# BLOCK2.net
KiCad netlist of a schematic drawn in Altium Designer
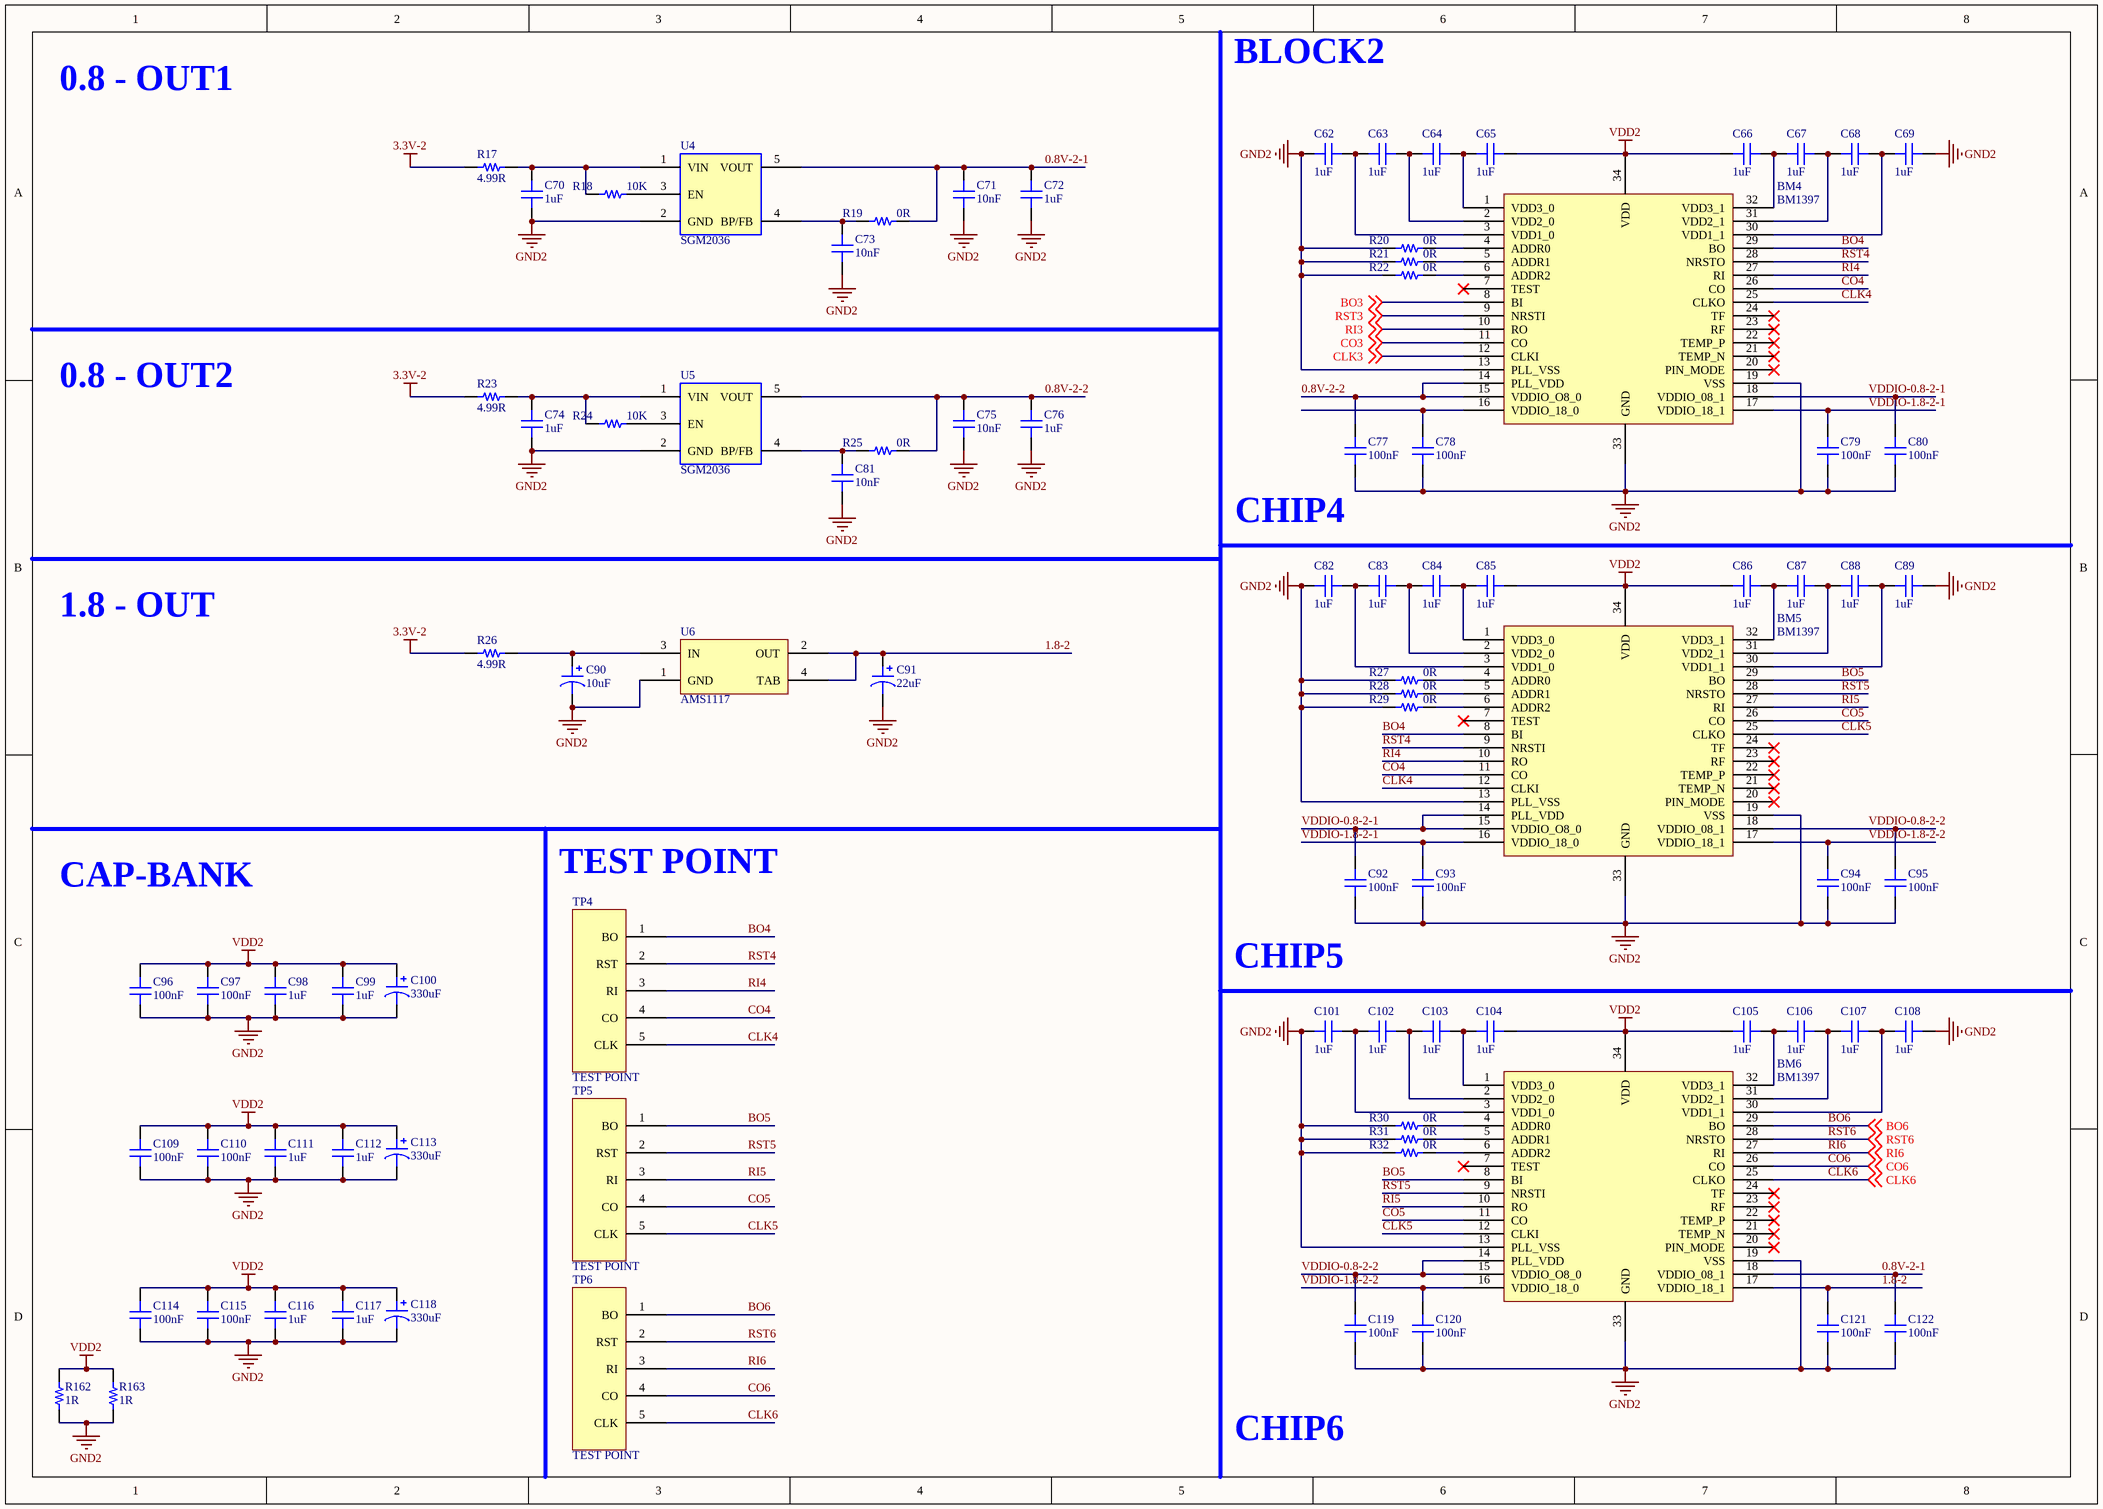
[diagram p0: BLOCK2.SchDoc]

(export (version "E")
  (design (tool "Eeschema 10.0.6"))
  (components
    (comp (ref "BM4") (value "BM1397") (footprint "BM1387") (libsource (lib "Miner_8TH") (part "BM1397_1")))
    (comp (ref "BM5") (value "BM1397") (footprint "BM1387") (libsource (lib "Miner_8TH") (part "BM1397_1")))
    (comp (ref "BM6") (value "BM1397") (footprint "BM1387") (libsource (lib "Miner_8TH") (part "BM1397_1")))
    (comp (ref "C62") (value "1uF") (footprint "CAP-SMD-0603") (libsource (lib "Miner_8TH") (part "CAP")))
    (comp (ref "C63") (value "1uF") (footprint "CAP-SMD-0603") (libsource (lib "Miner_8TH") (part "CAP")))
    (comp (ref "C64") (value "1uF") (footprint "CAP-SMD-0603") (libsource (lib "Miner_8TH") (part "CAP")))
    (comp (ref "C65") (value "1uF") (footprint "CAP-SMD-0603") (libsource (lib "Miner_8TH") (part "CAP")))
    (comp (ref "C66") (value "1uF") (footprint "CAP-SMD-0603") (libsource (lib "Miner_8TH") (part "CAP")))
    (comp (ref "C67") (value "1uF") (footprint "CAP-SMD-0603") (libsource (lib "Miner_8TH") (part "CAP")))
    (comp (ref "C68") (value "1uF") (footprint "CAP-SMD-0603") (libsource (lib "Miner_8TH") (part "CAP")))
    (comp (ref "C69") (value "1uF") (footprint "CAP-SMD-0603") (libsource (lib "Miner_8TH") (part "CAP")))
    (comp (ref "C70") (value "1uF") (footprint "CAP_SMD_0805") (libsource (lib "Miner_8TH") (part "CAP")))
    (comp (ref "C71") (value "10nF") (footprint "CAP_SMD_0805") (libsource (lib "Miner_8TH") (part "CAP")))
    (comp (ref "C72") (value "1uF") (footprint "CAP_SMD_0805") (libsource (lib "Miner_8TH") (part "CAP")))
    (comp (ref "C73") (value "10nF") (footprint "CAP_SMD_0805") (libsource (lib "Miner_8TH") (part "CAP")))
    (comp (ref "C74") (value "1uF") (footprint "CAP_SMD_0805") (libsource (lib "Miner_8TH") (part "CAP")))
    (comp (ref "C75") (value "10nF") (footprint "CAP_SMD_0805") (libsource (lib "Miner_8TH") (part "CAP")))
    (comp (ref "C76") (value "1uF") (footprint "CAP_SMD_0805") (libsource (lib "Miner_8TH") (part "CAP")))
    (comp (ref "C77") (value "100nF") (footprint "CAP_SMD_0805") (libsource (lib "Miner_8TH") (part "CAP")))
    (comp (ref "C78") (value "100nF") (footprint "CAP_SMD_0805") (libsource (lib "Miner_8TH") (part "CAP")))
    (comp (ref "C79") (value "100nF") (footprint "CAP_SMD_0805") (libsource (lib "Miner_8TH") (part "CAP")))
    (comp (ref "C80") (value "100nF") (footprint "CAP_SMD_0805") (libsource (lib "Miner_8TH") (part "CAP")))
    (comp (ref "C81") (value "10nF") (footprint "CAP_SMD_0805") (libsource (lib "Miner_8TH") (part "CAP")))
    (comp (ref "C82") (value "1uF") (footprint "CAP-SMD-0603") (libsource (lib "Miner_8TH") (part "CAP")))
    (comp (ref "C83") (value "1uF") (footprint "CAP-SMD-0603") (libsource (lib "Miner_8TH") (part "CAP")))
    (comp (ref "C84") (value "1uF") (footprint "CAP-SMD-0603") (libsource (lib "Miner_8TH") (part "CAP")))
    (comp (ref "C85") (value "1uF") (footprint "CAP-SMD-0603") (libsource (lib "Miner_8TH") (part "CAP")))
    (comp (ref "C86") (value "1uF") (footprint "CAP-SMD-0603") (libsource (lib "Miner_8TH") (part "CAP")))
    (comp (ref "C87") (value "1uF") (footprint "CAP-SMD-0603") (libsource (lib "Miner_8TH") (part "CAP")))
    (comp (ref "C88") (value "1uF") (footprint "CAP-SMD-0603") (libsource (lib "Miner_8TH") (part "CAP")))
    (comp (ref "C89") (value "1uF") (footprint "CAP-SMD-0603") (libsource (lib "Miner_8TH") (part "CAP")))
    (comp (ref "C90")
      (value "10uF")
      (footprint "CAP-TAN-CASE-A")
      (libsource (lib "Miner_8TH") (part "POLARIZED CAP"))
    )
    (comp (ref "C91")
      (value "22uF")
      (footprint "CAP-TAN-CASE-A")
      (libsource (lib "Miner_8TH") (part "POLARIZED CAP"))
    )
    (comp (ref "C92") (value "100nF") (footprint "CAP_SMD_0805") (libsource (lib "Miner_8TH") (part "CAP")))
    (comp (ref "C93") (value "100nF") (footprint "CAP_SMD_0805") (libsource (lib "Miner_8TH") (part "CAP")))
    (comp (ref "C94") (value "100nF") (footprint "CAP_SMD_0805") (libsource (lib "Miner_8TH") (part "CAP")))
    (comp (ref "C95") (value "100nF") (footprint "CAP_SMD_0805") (libsource (lib "Miner_8TH") (part "CAP")))
    (comp (ref "C96") (value "100nF") (footprint "CAP_SMD_0805") (libsource (lib "Miner_8TH") (part "CAP")))
    (comp (ref "C97") (value "100nF") (footprint "CAP_SMD_0805") (libsource (lib "Miner_8TH") (part "CAP")))
    (comp (ref "C98") (value "1uF") (footprint "CAP_SMD_0805") (libsource (lib "Miner_8TH") (part "CAP")))
    (comp (ref "C99") (value "1uF") (footprint "CAP_SMD_0805") (libsource (lib "Miner_8TH") (part "CAP")))
    (comp (ref "C100")
      (value "330uF")
      (footprint "CAP-TAN-CASE-E")
      (libsource (lib "Miner_8TH") (part "POLARIZED CAP"))
    )
    (comp (ref "C101") (value "1uF") (footprint "CAP-SMD-0603") (libsource (lib "Miner_8TH") (part "CAP")))
    (comp (ref "C102") (value "1uF") (footprint "CAP-SMD-0603") (libsource (lib "Miner_8TH") (part "CAP")))
    (comp (ref "C103") (value "1uF") (footprint "CAP-SMD-0603") (libsource (lib "Miner_8TH") (part "CAP")))
    (comp (ref "C104") (value "1uF") (footprint "CAP-SMD-0603") (libsource (lib "Miner_8TH") (part "CAP")))
    (comp (ref "C105") (value "1uF") (footprint "CAP-SMD-0603") (libsource (lib "Miner_8TH") (part "CAP")))
    (comp (ref "C106") (value "1uF") (footprint "CAP-SMD-0603") (libsource (lib "Miner_8TH") (part "CAP")))
    (comp (ref "C107") (value "1uF") (footprint "CAP-SMD-0603") (libsource (lib "Miner_8TH") (part "CAP")))
    (comp (ref "C108") (value "1uF") (footprint "CAP-SMD-0603") (libsource (lib "Miner_8TH") (part "CAP")))
    (comp (ref "C109") (value "100nF") (footprint "CAP_SMD_0805") (libsource (lib "Miner_8TH") (part "CAP")))
    (comp (ref "C110") (value "100nF") (footprint "CAP_SMD_0805") (libsource (lib "Miner_8TH") (part "CAP")))
    (comp (ref "C111") (value "1uF") (footprint "CAP_SMD_0805") (libsource (lib "Miner_8TH") (part "CAP")))
    (comp (ref "C112") (value "1uF") (footprint "CAP_SMD_0805") (libsource (lib "Miner_8TH") (part "CAP")))
    (comp (ref "C113")
      (value "330uF")
      (footprint "CAP-TAN-CASE-E")
      (libsource (lib "Miner_8TH") (part "POLARIZED CAP"))
    )
    (comp (ref "C114") (value "100nF") (footprint "CAP_SMD_0805") (libsource (lib "Miner_8TH") (part "CAP")))
    (comp (ref "C115") (value "100nF") (footprint "CAP_SMD_0805") (libsource (lib "Miner_8TH") (part "CAP")))
    (comp (ref "C116") (value "1uF") (footprint "CAP_SMD_0805") (libsource (lib "Miner_8TH") (part "CAP")))
    (comp (ref "C117") (value "1uF") (footprint "CAP_SMD_0805") (libsource (lib "Miner_8TH") (part "CAP")))
    (comp (ref "C118")
      (value "330uF")
      (footprint "CAP-TAN-CASE-E")
      (libsource (lib "Miner_8TH") (part "POLARIZED CAP"))
    )
    (comp (ref "C119") (value "100nF") (footprint "CAP_SMD_0805") (libsource (lib "Miner_8TH") (part "CAP")))
    (comp (ref "C120") (value "100nF") (footprint "CAP_SMD_0805") (libsource (lib "Miner_8TH") (part "CAP")))
    (comp (ref "C121") (value "100nF") (footprint "CAP_SMD_0805") (libsource (lib "Miner_8TH") (part "CAP")))
    (comp (ref "C122") (value "100nF") (footprint "CAP_SMD_0805") (libsource (lib "Miner_8TH") (part "CAP")))
    (comp (ref "R17") (value "4.99R") (footprint "RES-SMD-1206") (libsource (lib "Miner_8TH") (part "RES")))
    (comp (ref "R18") (value "10K") (footprint "RES-SMD-0402") (libsource (lib "Miner_8TH") (part "RES")))
    (comp (ref "R19") (value "0R") (footprint "RES-SMD-0402") (libsource (lib "Miner_8TH") (part "RES")))
    (comp (ref "R20") (value "0R") (footprint "RES-SMD-0402") (libsource (lib "Miner_8TH") (part "RES")))
    (comp (ref "R21") (value "0R") (footprint "RES-SMD-0402") (libsource (lib "Miner_8TH") (part "RES")))
    (comp (ref "R22") (value "0R") (footprint "RES-SMD-0402") (libsource (lib "Miner_8TH") (part "RES")))
    (comp (ref "R23") (value "4.99R") (footprint "RES-SMD-1206") (libsource (lib "Miner_8TH") (part "RES")))
    (comp (ref "R24") (value "10K") (footprint "RES-SMD-0402") (libsource (lib "Miner_8TH") (part "RES")))
    (comp (ref "R25") (value "0R") (footprint "RES-SMD-0402") (libsource (lib "Miner_8TH") (part "RES")))
    (comp (ref "R26") (value "4.99R") (footprint "RES-SMD-1206") (libsource (lib "Miner_8TH") (part "RES")))
    (comp (ref "R27") (value "0R") (footprint "RES-SMD-0402") (libsource (lib "Miner_8TH") (part "RES")))
    (comp (ref "R28") (value "0R") (footprint "RES-SMD-0402") (libsource (lib "Miner_8TH") (part "RES")))
    (comp (ref "R29") (value "0R") (footprint "RES-SMD-0402") (libsource (lib "Miner_8TH") (part "RES")))
    (comp (ref "R30") (value "0R") (footprint "RES-SMD-0402") (libsource (lib "Miner_8TH") (part "RES")))
    (comp (ref "R31") (value "0R") (footprint "RES-SMD-0402") (libsource (lib "Miner_8TH") (part "RES")))
    (comp (ref "R32") (value "0R") (footprint "RES-SMD-0402") (libsource (lib "Miner_8TH") (part "RES")))
    (comp (ref "R162") (value "1R") (footprint "RES-SMD-1210") (libsource (lib "Miner_8TH") (part "RES")))
    (comp (ref "R163") (value "1R") (footprint "RES-SMD-1210") (libsource (lib "Miner_8TH") (part "RES")))
    (comp (ref "TP4")
      (value "TEST POINT")
      (footprint "TEST_POINT")
      (libsource (lib "Miner_8TH") (part "TEST POINT"))
    )
    (comp (ref "TP5")
      (value "TEST POINT")
      (footprint "TEST_POINT")
      (libsource (lib "Miner_8TH") (part "TEST POINT"))
    )
    (comp (ref "TP6")
      (value "TEST POINT")
      (footprint "TEST_POINT")
      (libsource (lib "Miner_8TH") (part "TEST POINT"))
    )
    (comp (ref "U4")
      (value "SGM2036")
      (footprint "SOT23-5PIN")
      (libsource (lib "Miner_8TH") (part "SGM2036"))
    )
    (comp (ref "U5")
      (value "SGM2036")
      (footprint "SOT23-5PIN")
      (libsource (lib "Miner_8TH") (part "SGM2036"))
    )
    (comp (ref "U6") (value "AMS1117") (footprint "AMS1117") (libsource (lib "Miner_8TH") (part "AMS1117")))
  )
  (nets
    (net (code "1") (name "/0.8V-2-1") (class "Default")
      (node (ref "BM6") (pin "18") (pinfunction "VDDIO_08_1_18") (pintype "passive"))
      (node (ref "C122") (pin "2") (pinfunction "2_2") (pintype "passive"))
      (node (ref "C71") (pin "2") (pinfunction "2_2") (pintype "passive"))
      (node (ref "C72") (pin "2") (pinfunction "2_2") (pintype "passive"))
      (node (ref "R19") (pin "2") (pinfunction "2_2") (pintype "passive"))
      (node (ref "U4") (pin "5") (pinfunction "VOUT_5") (pintype "passive"))
    )
    (net (code "2") (name "/0.8V-2-2") (class "Default")
      (node (ref "BM4") (pin "14") (pinfunction "PLL_VDD_14") (pintype "passive"))
      (node (ref "BM4") (pin "15") (pinfunction "VDDIO_O8_0_15") (pintype "passive"))
      (node (ref "C75") (pin "2") (pinfunction "2_2") (pintype "passive"))
      (node (ref "C76") (pin "2") (pinfunction "2_2") (pintype "passive"))
      (node (ref "C77") (pin "2") (pinfunction "2_2") (pintype "passive"))
      (node (ref "R25") (pin "2") (pinfunction "2_2") (pintype "passive"))
      (node (ref "U5") (pin "5") (pinfunction "VOUT_5") (pintype "passive"))
    )
    (net (code "3") (name "/1.8-2") (class "Default")
      (node (ref "BM6") (pin "17") (pinfunction "VDDIO_18_1_17") (pintype "passive"))
      (node (ref "C121") (pin "2") (pinfunction "2_2") (pintype "passive"))
      (node (ref "C91") (pin "1") (pinfunction "1_1") (pintype "passive"))
      (node (ref "U6") (pin "2") (pinfunction "OUT_2") (pintype "passive"))
      (node (ref "U6") (pin "4") (pinfunction "TAB_4") (pintype "passive"))
    )
    (net (code "4") (name "/BO4") (class "Default")
      (node (ref "BM4") (pin "29") (pinfunction "BO_29") (pintype "passive"))
      (node (ref "BM5") (pin "8") (pinfunction "BI_8") (pintype "passive"))
      (node (ref "TP4") (pin "1") (pinfunction "BO_1") (pintype "passive"))
    )
    (net (code "5") (name "/BO5") (class "Default")
      (node (ref "BM5") (pin "29") (pinfunction "BO_29") (pintype "passive"))
      (node (ref "BM6") (pin "8") (pinfunction "BI_8") (pintype "passive"))
      (node (ref "TP5") (pin "1") (pinfunction "BO_1") (pintype "passive"))
    )
    (net (code "6") (name "/CLK4") (class "Default")
      (node (ref "BM4") (pin "25") (pinfunction "CLKO_25") (pintype "passive"))
      (node (ref "BM5") (pin "12") (pinfunction "CLKI_12") (pintype "passive"))
      (node (ref "TP4") (pin "5") (pinfunction "CLK_5") (pintype "passive"))
    )
    (net (code "7") (name "/CLK5") (class "Default")
      (node (ref "BM5") (pin "25") (pinfunction "CLKO_25") (pintype "passive"))
      (node (ref "BM6") (pin "12") (pinfunction "CLKI_12") (pintype "passive"))
      (node (ref "TP5") (pin "5") (pinfunction "CLK_5") (pintype "passive"))
    )
    (net (code "8") (name "/CO4") (class "Default")
      (node (ref "BM4") (pin "26") (pinfunction "CO_26") (pintype "passive"))
      (node (ref "BM5") (pin "11") (pinfunction "CO_11") (pintype "passive"))
      (node (ref "TP4") (pin "4") (pinfunction "CO_4") (pintype "passive"))
    )
    (net (code "9") (name "/CO5") (class "Default")
      (node (ref "BM5") (pin "26") (pinfunction "CO_26") (pintype "passive"))
      (node (ref "BM6") (pin "11") (pinfunction "CO_11") (pintype "passive"))
      (node (ref "TP5") (pin "4") (pinfunction "CO_4") (pintype "passive"))
    )
    (net (code "10") (name "/RI4") (class "Default")
      (node (ref "BM4") (pin "27") (pinfunction "RI_27") (pintype "passive"))
      (node (ref "BM5") (pin "10") (pinfunction "RO_10") (pintype "passive"))
      (node (ref "TP4") (pin "3") (pinfunction "RI_3") (pintype "passive"))
    )
    (net (code "11") (name "/RI5") (class "Default")
      (node (ref "BM5") (pin "27") (pinfunction "RI_27") (pintype "passive"))
      (node (ref "BM6") (pin "10") (pinfunction "RO_10") (pintype "passive"))
      (node (ref "TP5") (pin "3") (pinfunction "RI_3") (pintype "passive"))
    )
    (net (code "12") (name "/RST4") (class "Default")
      (node (ref "BM4") (pin "28") (pinfunction "NRSTO_28") (pintype "passive"))
      (node (ref "BM5") (pin "9") (pinfunction "NRSTI_9") (pintype "passive"))
      (node (ref "TP4") (pin "2") (pinfunction "RST_2") (pintype "passive"))
    )
    (net (code "13") (name "/RST5") (class "Default")
      (node (ref "BM5") (pin "28") (pinfunction "NRSTO_28") (pintype "passive"))
      (node (ref "BM6") (pin "9") (pinfunction "NRSTI_9") (pintype "passive"))
      (node (ref "TP5") (pin "2") (pinfunction "RST_2") (pintype "passive"))
    )
    (net (code "14") (name "/VDDIO-0.8-2-1") (class "Default")
      (node (ref "BM4") (pin "18") (pinfunction "VDDIO_08_1_18") (pintype "passive"))
      (node (ref "BM5") (pin "14") (pinfunction "PLL_VDD_14") (pintype "passive"))
      (node (ref "BM5") (pin "15") (pinfunction "VDDIO_O8_0_15") (pintype "passive"))
      (node (ref "C80") (pin "2") (pinfunction "2_2") (pintype "passive"))
      (node (ref "C92") (pin "2") (pinfunction "2_2") (pintype "passive"))
    )
    (net (code "15") (name "/VDDIO-0.8-2-2") (class "Default")
      (node (ref "BM5") (pin "18") (pinfunction "VDDIO_08_1_18") (pintype "passive"))
      (node (ref "BM6") (pin "14") (pinfunction "PLL_VDD_14") (pintype "passive"))
      (node (ref "BM6") (pin "15") (pinfunction "VDDIO_O8_0_15") (pintype "passive"))
      (node (ref "C119") (pin "2") (pinfunction "2_2") (pintype "passive"))
      (node (ref "C95") (pin "2") (pinfunction "2_2") (pintype "passive"))
    )
    (net (code "16") (name "/VDDIO-1.8-2-1") (class "Default")
      (node (ref "BM4") (pin "17") (pinfunction "VDDIO_18_1_17") (pintype "passive"))
      (node (ref "BM5") (pin "16") (pinfunction "VDDIO_18_0_16") (pintype "passive"))
      (node (ref "C79") (pin "2") (pinfunction "2_2") (pintype "passive"))
      (node (ref "C93") (pin "2") (pinfunction "2_2") (pintype "passive"))
    )
    (net (code "17") (name "/VDDIO-1.8-2-2") (class "Default")
      (node (ref "BM5") (pin "17") (pinfunction "VDDIO_18_1_17") (pintype "passive"))
      (node (ref "BM6") (pin "16") (pinfunction "VDDIO_18_0_16") (pintype "passive"))
      (node (ref "C120") (pin "2") (pinfunction "2_2") (pintype "passive"))
      (node (ref "C94") (pin "2") (pinfunction "2_2") (pintype "passive"))
    )
    (net (code "18") (name "3.3V-2") (class "Default")
      (node (ref "R17") (pin "1") (pinfunction "1_1") (pintype "passive"))
      (node (ref "R23") (pin "1") (pinfunction "1_1") (pintype "passive"))
      (node (ref "R26") (pin "1") (pinfunction "1_1") (pintype "passive"))
    )
    (net (code "19") (name "BO3") (class "Default")
      (node (ref "BM4") (pin "8") (pinfunction "BI_8") (pintype "passive"))
    )
    (net (code "20") (name "BO6") (class "Default")
      (node (ref "BM6") (pin "29") (pinfunction "BO_29") (pintype "passive"))
      (node (ref "TP6") (pin "1") (pinfunction "BO_1") (pintype "passive"))
    )
    (net (code "21") (name "CLK3") (class "Default")
      (node (ref "BM4") (pin "12") (pinfunction "CLKI_12") (pintype "passive"))
    )
    (net (code "22") (name "CLK6") (class "Default")
      (node (ref "BM6") (pin "25") (pinfunction "CLKO_25") (pintype "passive"))
      (node (ref "TP6") (pin "5") (pinfunction "CLK_5") (pintype "passive"))
    )
    (net (code "23") (name "CO3") (class "Default")
      (node (ref "BM4") (pin "11") (pinfunction "CO_11") (pintype "passive"))
    )
    (net (code "24") (name "CO6") (class "Default")
      (node (ref "BM6") (pin "26") (pinfunction "CO_26") (pintype "passive"))
      (node (ref "TP6") (pin "4") (pinfunction "CO_4") (pintype "passive"))
    )
    (net (code "25") (name "GND2") (class "Default")
      (node (ref "BM4") (pin "13") (pinfunction "PLL_VSS_13") (pintype "passive"))
      (node (ref "BM4") (pin "19") (pinfunction "VSS_19") (pintype "passive"))
      (node (ref "BM4") (pin "33") (pinfunction "GND_33") (pintype "passive"))
      (node (ref "BM5") (pin "13") (pinfunction "PLL_VSS_13") (pintype "passive"))
      (node (ref "BM5") (pin "19") (pinfunction "VSS_19") (pintype "passive"))
      (node (ref "BM5") (pin "33") (pinfunction "GND_33") (pintype "passive"))
      (node (ref "BM6") (pin "13") (pinfunction "PLL_VSS_13") (pintype "passive"))
      (node (ref "BM6") (pin "19") (pinfunction "VSS_19") (pintype "passive"))
      (node (ref "BM6") (pin "33") (pinfunction "GND_33") (pintype "passive"))
      (node (ref "C100") (pin "2") (pinfunction "2_2") (pintype "passive"))
      (node (ref "C101") (pin "1") (pinfunction "1_1") (pintype "passive"))
      (node (ref "C108") (pin "2") (pinfunction "2_2") (pintype "passive"))
      (node (ref "C109") (pin "1") (pinfunction "1_1") (pintype "passive"))
      (node (ref "C110") (pin "1") (pinfunction "1_1") (pintype "passive"))
      (node (ref "C111") (pin "1") (pinfunction "1_1") (pintype "passive"))
      (node (ref "C112") (pin "1") (pinfunction "1_1") (pintype "passive"))
      (node (ref "C113") (pin "2") (pinfunction "2_2") (pintype "passive"))
      (node (ref "C114") (pin "1") (pinfunction "1_1") (pintype "passive"))
      (node (ref "C115") (pin "1") (pinfunction "1_1") (pintype "passive"))
      (node (ref "C116") (pin "1") (pinfunction "1_1") (pintype "passive"))
      (node (ref "C117") (pin "1") (pinfunction "1_1") (pintype "passive"))
      (node (ref "C118") (pin "2") (pinfunction "2_2") (pintype "passive"))
      (node (ref "C119") (pin "1") (pinfunction "1_1") (pintype "passive"))
      (node (ref "C120") (pin "1") (pinfunction "1_1") (pintype "passive"))
      (node (ref "C121") (pin "1") (pinfunction "1_1") (pintype "passive"))
      (node (ref "C122") (pin "1") (pinfunction "1_1") (pintype "passive"))
      (node (ref "C62") (pin "1") (pinfunction "1_1") (pintype "passive"))
      (node (ref "C69") (pin "2") (pinfunction "2_2") (pintype "passive"))
      (node (ref "C70") (pin "1") (pinfunction "1_1") (pintype "passive"))
      (node (ref "C71") (pin "1") (pinfunction "1_1") (pintype "passive"))
      (node (ref "C72") (pin "1") (pinfunction "1_1") (pintype "passive"))
      (node (ref "C73") (pin "1") (pinfunction "1_1") (pintype "passive"))
      (node (ref "C74") (pin "1") (pinfunction "1_1") (pintype "passive"))
      (node (ref "C75") (pin "1") (pinfunction "1_1") (pintype "passive"))
      (node (ref "C76") (pin "1") (pinfunction "1_1") (pintype "passive"))
      (node (ref "C77") (pin "1") (pinfunction "1_1") (pintype "passive"))
      (node (ref "C78") (pin "1") (pinfunction "1_1") (pintype "passive"))
      (node (ref "C79") (pin "1") (pinfunction "1_1") (pintype "passive"))
      (node (ref "C80") (pin "1") (pinfunction "1_1") (pintype "passive"))
      (node (ref "C81") (pin "1") (pinfunction "1_1") (pintype "passive"))
      (node (ref "C82") (pin "1") (pinfunction "1_1") (pintype "passive"))
      (node (ref "C89") (pin "2") (pinfunction "2_2") (pintype "passive"))
      (node (ref "C90") (pin "2") (pinfunction "2_2") (pintype "passive"))
      (node (ref "C91") (pin "2") (pinfunction "2_2") (pintype "passive"))
      (node (ref "C92") (pin "1") (pinfunction "1_1") (pintype "passive"))
      (node (ref "C93") (pin "1") (pinfunction "1_1") (pintype "passive"))
      (node (ref "C94") (pin "1") (pinfunction "1_1") (pintype "passive"))
      (node (ref "C95") (pin "1") (pinfunction "1_1") (pintype "passive"))
      (node (ref "C96") (pin "1") (pinfunction "1_1") (pintype "passive"))
      (node (ref "C97") (pin "1") (pinfunction "1_1") (pintype "passive"))
      (node (ref "C98") (pin "1") (pinfunction "1_1") (pintype "passive"))
      (node (ref "C99") (pin "1") (pinfunction "1_1") (pintype "passive"))
      (node (ref "R162") (pin "1") (pinfunction "1_1") (pintype "passive"))
      (node (ref "R163") (pin "1") (pinfunction "1_1") (pintype "passive"))
      (node (ref "R20") (pin "1") (pinfunction "1_1") (pintype "passive"))
      (node (ref "R21") (pin "1") (pinfunction "1_1") (pintype "passive"))
      (node (ref "R22") (pin "1") (pinfunction "1_1") (pintype "passive"))
      (node (ref "R27") (pin "1") (pinfunction "1_1") (pintype "passive"))
      (node (ref "R28") (pin "1") (pinfunction "1_1") (pintype "passive"))
      (node (ref "R29") (pin "1") (pinfunction "1_1") (pintype "passive"))
      (node (ref "R30") (pin "1") (pinfunction "1_1") (pintype "passive"))
      (node (ref "R31") (pin "1") (pinfunction "1_1") (pintype "passive"))
      (node (ref "R32") (pin "1") (pinfunction "1_1") (pintype "passive"))
      (node (ref "U4") (pin "2") (pinfunction "GND_2") (pintype "passive"))
      (node (ref "U5") (pin "2") (pinfunction "GND_2") (pintype "passive"))
      (node (ref "U6") (pin "1") (pinfunction "GND_1") (pintype "passive"))
    )
    (net (code "26") (name "Net-(BM4-ADDR0)") (class "Default")
      (node (ref "BM4") (pin "4") (pinfunction "ADDR0_4") (pintype "passive"))
      (node (ref "R20") (pin "2") (pinfunction "2_2") (pintype "passive"))
    )
    (net (code "27") (name "Net-(BM4-ADDR1)") (class "Default")
      (node (ref "BM4") (pin "5") (pinfunction "ADDR1_5") (pintype "passive"))
      (node (ref "R21") (pin "2") (pinfunction "2_2") (pintype "passive"))
    )
    (net (code "28") (name "Net-(BM4-ADDR2)") (class "Default")
      (node (ref "BM4") (pin "6") (pinfunction "ADDR2_6") (pintype "passive"))
      (node (ref "R22") (pin "2") (pinfunction "2_2") (pintype "passive"))
    )
    (net (code "29") (name "Net-(BM4-VDD1_0)") (class "Default")
      (node (ref "BM4") (pin "3") (pinfunction "VDD1_0_3") (pintype "passive"))
      (node (ref "C62") (pin "2") (pinfunction "2_2") (pintype "passive"))
      (node (ref "C63") (pin "1") (pinfunction "1_1") (pintype "passive"))
    )
    (net (code "30") (name "Net-(BM4-VDD1_1)") (class "Default")
      (node (ref "BM4") (pin "30") (pinfunction "VDD1_1_30") (pintype "passive"))
      (node (ref "C68") (pin "2") (pinfunction "2_2") (pintype "passive"))
      (node (ref "C69") (pin "1") (pinfunction "1_1") (pintype "passive"))
    )
    (net (code "31") (name "Net-(BM4-VDD2_0)") (class "Default")
      (node (ref "BM4") (pin "2") (pinfunction "VDD2_0_2") (pintype "passive"))
      (node (ref "C63") (pin "2") (pinfunction "2_2") (pintype "passive"))
      (node (ref "C64") (pin "1") (pinfunction "1_1") (pintype "passive"))
    )
    (net (code "32") (name "Net-(BM4-VDD2_1)") (class "Default")
      (node (ref "BM4") (pin "31") (pinfunction "VDD2_1_31") (pintype "passive"))
      (node (ref "C67") (pin "2") (pinfunction "2_2") (pintype "passive"))
      (node (ref "C68") (pin "1") (pinfunction "1_1") (pintype "passive"))
    )
    (net (code "33") (name "Net-(BM4-VDD3_0)") (class "Default")
      (node (ref "BM4") (pin "1") (pinfunction "VDD3_0_1") (pintype "passive"))
      (node (ref "C64") (pin "2") (pinfunction "2_2") (pintype "passive"))
      (node (ref "C65") (pin "1") (pinfunction "1_1") (pintype "passive"))
    )
    (net (code "34") (name "Net-(BM4-VDD3_1)") (class "Default")
      (node (ref "BM4") (pin "32") (pinfunction "VDD3_1_32") (pintype "passive"))
      (node (ref "C66") (pin "2") (pinfunction "2_2") (pintype "passive"))
      (node (ref "C67") (pin "1") (pinfunction "1_1") (pintype "passive"))
    )
    (net (code "35") (name "Net-(BM4-VDDIO_18_0)") (class "Default")
      (node (ref "BM4") (pin "16") (pinfunction "VDDIO_18_0_16") (pintype "passive"))
      (node (ref "C78") (pin "2") (pinfunction "2_2") (pintype "passive"))
    )
    (net (code "36") (name "Net-(BM5-ADDR0)") (class "Default")
      (node (ref "BM5") (pin "4") (pinfunction "ADDR0_4") (pintype "passive"))
      (node (ref "R27") (pin "2") (pinfunction "2_2") (pintype "passive"))
    )
    (net (code "37") (name "Net-(BM5-ADDR1)") (class "Default")
      (node (ref "BM5") (pin "5") (pinfunction "ADDR1_5") (pintype "passive"))
      (node (ref "R28") (pin "2") (pinfunction "2_2") (pintype "passive"))
    )
    (net (code "38") (name "Net-(BM5-ADDR2)") (class "Default")
      (node (ref "BM5") (pin "6") (pinfunction "ADDR2_6") (pintype "passive"))
      (node (ref "R29") (pin "2") (pinfunction "2_2") (pintype "passive"))
    )
    (net (code "39") (name "Net-(BM5-VDD1_0)") (class "Default")
      (node (ref "BM5") (pin "3") (pinfunction "VDD1_0_3") (pintype "passive"))
      (node (ref "C82") (pin "2") (pinfunction "2_2") (pintype "passive"))
      (node (ref "C83") (pin "1") (pinfunction "1_1") (pintype "passive"))
    )
    (net (code "40") (name "Net-(BM5-VDD1_1)") (class "Default")
      (node (ref "BM5") (pin "30") (pinfunction "VDD1_1_30") (pintype "passive"))
      (node (ref "C88") (pin "2") (pinfunction "2_2") (pintype "passive"))
      (node (ref "C89") (pin "1") (pinfunction "1_1") (pintype "passive"))
    )
    (net (code "41") (name "Net-(BM5-VDD2_0)") (class "Default")
      (node (ref "BM5") (pin "2") (pinfunction "VDD2_0_2") (pintype "passive"))
      (node (ref "C83") (pin "2") (pinfunction "2_2") (pintype "passive"))
      (node (ref "C84") (pin "1") (pinfunction "1_1") (pintype "passive"))
    )
    (net (code "42") (name "Net-(BM5-VDD2_1)") (class "Default")
      (node (ref "BM5") (pin "31") (pinfunction "VDD2_1_31") (pintype "passive"))
      (node (ref "C87") (pin "2") (pinfunction "2_2") (pintype "passive"))
      (node (ref "C88") (pin "1") (pinfunction "1_1") (pintype "passive"))
    )
    (net (code "43") (name "Net-(BM5-VDD3_0)") (class "Default")
      (node (ref "BM5") (pin "1") (pinfunction "VDD3_0_1") (pintype "passive"))
      (node (ref "C84") (pin "2") (pinfunction "2_2") (pintype "passive"))
      (node (ref "C85") (pin "1") (pinfunction "1_1") (pintype "passive"))
    )
    (net (code "44") (name "Net-(BM5-VDD3_1)") (class "Default")
      (node (ref "BM5") (pin "32") (pinfunction "VDD3_1_32") (pintype "passive"))
      (node (ref "C86") (pin "2") (pinfunction "2_2") (pintype "passive"))
      (node (ref "C87") (pin "1") (pinfunction "1_1") (pintype "passive"))
    )
    (net (code "45") (name "Net-(BM6-ADDR0)") (class "Default")
      (node (ref "BM6") (pin "4") (pinfunction "ADDR0_4") (pintype "passive"))
      (node (ref "R30") (pin "2") (pinfunction "2_2") (pintype "passive"))
    )
    (net (code "46") (name "Net-(BM6-ADDR1)") (class "Default")
      (node (ref "BM6") (pin "5") (pinfunction "ADDR1_5") (pintype "passive"))
      (node (ref "R31") (pin "2") (pinfunction "2_2") (pintype "passive"))
    )
    (net (code "47") (name "Net-(BM6-ADDR2)") (class "Default")
      (node (ref "BM6") (pin "6") (pinfunction "ADDR2_6") (pintype "passive"))
      (node (ref "R32") (pin "2") (pinfunction "2_2") (pintype "passive"))
    )
    (net (code "48") (name "Net-(BM6-VDD1_0)") (class "Default")
      (node (ref "BM6") (pin "3") (pinfunction "VDD1_0_3") (pintype "passive"))
      (node (ref "C101") (pin "2") (pinfunction "2_2") (pintype "passive"))
      (node (ref "C102") (pin "1") (pinfunction "1_1") (pintype "passive"))
    )
    (net (code "49") (name "Net-(BM6-VDD1_1)") (class "Default")
      (node (ref "BM6") (pin "30") (pinfunction "VDD1_1_30") (pintype "passive"))
      (node (ref "C107") (pin "2") (pinfunction "2_2") (pintype "passive"))
      (node (ref "C108") (pin "1") (pinfunction "1_1") (pintype "passive"))
    )
    (net (code "50") (name "Net-(BM6-VDD2_0)") (class "Default")
      (node (ref "BM6") (pin "2") (pinfunction "VDD2_0_2") (pintype "passive"))
      (node (ref "C102") (pin "2") (pinfunction "2_2") (pintype "passive"))
      (node (ref "C103") (pin "1") (pinfunction "1_1") (pintype "passive"))
    )
    (net (code "51") (name "Net-(BM6-VDD2_1)") (class "Default")
      (node (ref "BM6") (pin "31") (pinfunction "VDD2_1_31") (pintype "passive"))
      (node (ref "C106") (pin "2") (pinfunction "2_2") (pintype "passive"))
      (node (ref "C107") (pin "1") (pinfunction "1_1") (pintype "passive"))
    )
    (net (code "52") (name "Net-(BM6-VDD3_0)") (class "Default")
      (node (ref "BM6") (pin "1") (pinfunction "VDD3_0_1") (pintype "passive"))
      (node (ref "C103") (pin "2") (pinfunction "2_2") (pintype "passive"))
      (node (ref "C104") (pin "1") (pinfunction "1_1") (pintype "passive"))
    )
    (net (code "53") (name "Net-(BM6-VDD3_1)") (class "Default")
      (node (ref "BM6") (pin "32") (pinfunction "VDD3_1_32") (pintype "passive"))
      (node (ref "C105") (pin "2") (pinfunction "2_2") (pintype "passive"))
      (node (ref "C106") (pin "1") (pinfunction "1_1") (pintype "passive"))
    )
    (net (code "54") (name "Net-(U4-BP{slash}FB)") (class "Default")
      (node (ref "C73") (pin "2") (pinfunction "2_2") (pintype "passive"))
      (node (ref "R19") (pin "1") (pinfunction "1_1") (pintype "passive"))
      (node (ref "U4") (pin "4") (pinfunction "BP/FB_4") (pintype "passive"))
    )
    (net (code "55") (name "Net-(U4-EN)") (class "Default")
      (node (ref "R18") (pin "2") (pinfunction "2_2") (pintype "passive"))
      (node (ref "U4") (pin "3") (pinfunction "EN_3") (pintype "passive"))
    )
    (net (code "56") (name "Net-(U4-VIN)") (class "Default")
      (node (ref "C70") (pin "2") (pinfunction "2_2") (pintype "passive"))
      (node (ref "R17") (pin "2") (pinfunction "2_2") (pintype "passive"))
      (node (ref "R18") (pin "1") (pinfunction "1_1") (pintype "passive"))
      (node (ref "U4") (pin "1") (pinfunction "VIN_1") (pintype "passive"))
    )
    (net (code "57") (name "Net-(U5-BP{slash}FB)") (class "Default")
      (node (ref "C81") (pin "2") (pinfunction "2_2") (pintype "passive"))
      (node (ref "R25") (pin "1") (pinfunction "1_1") (pintype "passive"))
      (node (ref "U5") (pin "4") (pinfunction "BP/FB_4") (pintype "passive"))
    )
    (net (code "58") (name "Net-(U5-EN)") (class "Default")
      (node (ref "R24") (pin "2") (pinfunction "2_2") (pintype "passive"))
      (node (ref "U5") (pin "3") (pinfunction "EN_3") (pintype "passive"))
    )
    (net (code "59") (name "Net-(U5-VIN)") (class "Default")
      (node (ref "C74") (pin "2") (pinfunction "2_2") (pintype "passive"))
      (node (ref "R23") (pin "2") (pinfunction "2_2") (pintype "passive"))
      (node (ref "R24") (pin "1") (pinfunction "1_1") (pintype "passive"))
      (node (ref "U5") (pin "1") (pinfunction "VIN_1") (pintype "passive"))
    )
    (net (code "60") (name "Net-(U6-IN)") (class "Default")
      (node (ref "C90") (pin "1") (pinfunction "1_1") (pintype "passive"))
      (node (ref "R26") (pin "2") (pinfunction "2_2") (pintype "passive"))
      (node (ref "U6") (pin "3") (pinfunction "IN_3") (pintype "passive"))
    )
    (net (code "61") (name "RI3") (class "Default")
      (node (ref "BM4") (pin "10") (pinfunction "RO_10") (pintype "passive"))
    )
    (net (code "62") (name "RI6") (class "Default")
      (node (ref "BM6") (pin "27") (pinfunction "RI_27") (pintype "passive"))
      (node (ref "TP6") (pin "3") (pinfunction "RI_3") (pintype "passive"))
    )
    (net (code "63") (name "RST3") (class "Default")
      (node (ref "BM4") (pin "9") (pinfunction "NRSTI_9") (pintype "passive"))
    )
    (net (code "64") (name "RST6") (class "Default")
      (node (ref "BM6") (pin "28") (pinfunction "NRSTO_28") (pintype "passive"))
      (node (ref "TP6") (pin "2") (pinfunction "RST_2") (pintype "passive"))
    )
    (net (code "65") (name "VDD2") (class "Default")
      (node (ref "BM4") (pin "34") (pinfunction "VDD_34") (pintype "passive"))
      (node (ref "BM5") (pin "34") (pinfunction "VDD_34") (pintype "passive"))
      (node (ref "BM6") (pin "34") (pinfunction "VDD_34") (pintype "passive"))
      (node (ref "C100") (pin "1") (pinfunction "1_1") (pintype "passive"))
      (node (ref "C104") (pin "2") (pinfunction "2_2") (pintype "passive"))
      (node (ref "C105") (pin "1") (pinfunction "1_1") (pintype "passive"))
      (node (ref "C109") (pin "2") (pinfunction "2_2") (pintype "passive"))
      (node (ref "C110") (pin "2") (pinfunction "2_2") (pintype "passive"))
      (node (ref "C111") (pin "2") (pinfunction "2_2") (pintype "passive"))
      (node (ref "C112") (pin "2") (pinfunction "2_2") (pintype "passive"))
      (node (ref "C113") (pin "1") (pinfunction "1_1") (pintype "passive"))
      (node (ref "C114") (pin "2") (pinfunction "2_2") (pintype "passive"))
      (node (ref "C115") (pin "2") (pinfunction "2_2") (pintype "passive"))
      (node (ref "C116") (pin "2") (pinfunction "2_2") (pintype "passive"))
      (node (ref "C117") (pin "2") (pinfunction "2_2") (pintype "passive"))
      (node (ref "C118") (pin "1") (pinfunction "1_1") (pintype "passive"))
      (node (ref "C65") (pin "2") (pinfunction "2_2") (pintype "passive"))
      (node (ref "C66") (pin "1") (pinfunction "1_1") (pintype "passive"))
      (node (ref "C85") (pin "2") (pinfunction "2_2") (pintype "passive"))
      (node (ref "C86") (pin "1") (pinfunction "1_1") (pintype "passive"))
      (node (ref "C96") (pin "2") (pinfunction "2_2") (pintype "passive"))
      (node (ref "C97") (pin "2") (pinfunction "2_2") (pintype "passive"))
      (node (ref "C98") (pin "2") (pinfunction "2_2") (pintype "passive"))
      (node (ref "C99") (pin "2") (pinfunction "2_2") (pintype "passive"))
      (node (ref "R162") (pin "2") (pinfunction "2_2") (pintype "passive"))
      (node (ref "R163") (pin "2") (pinfunction "2_2") (pintype "passive"))
    )
    (net (code "66") (name "unconnected-(BM4-PIN_MODE-Pad20)") (class "Default")
      (node (ref "BM4") (pin "20") (pinfunction "PIN_MODE_20") (pintype "passive+no_connect"))
    )
    (net (code "67") (name "unconnected-(BM4-RF-Pad23)") (class "Default")
      (node (ref "BM4") (pin "23") (pinfunction "RF_23") (pintype "passive+no_connect"))
    )
    (net (code "68") (name "unconnected-(BM4-TEMP_N-Pad21)") (class "Default")
      (node (ref "BM4") (pin "21") (pinfunction "TEMP_N_21") (pintype "passive+no_connect"))
    )
    (net (code "69") (name "unconnected-(BM4-TEMP_P-Pad22)") (class "Default")
      (node (ref "BM4") (pin "22") (pinfunction "TEMP_P_22") (pintype "passive+no_connect"))
    )
    (net (code "70") (name "unconnected-(BM4-TEST-Pad7)") (class "Default")
      (node (ref "BM4") (pin "7") (pinfunction "TEST_7") (pintype "passive+no_connect"))
    )
    (net (code "71") (name "unconnected-(BM4-TF-Pad24)") (class "Default")
      (node (ref "BM4") (pin "24") (pinfunction "TF_24") (pintype "passive+no_connect"))
    )
    (net (code "72") (name "unconnected-(BM5-PIN_MODE-Pad20)") (class "Default")
      (node (ref "BM5") (pin "20") (pinfunction "PIN_MODE_20") (pintype "passive+no_connect"))
    )
    (net (code "73") (name "unconnected-(BM5-RF-Pad23)") (class "Default")
      (node (ref "BM5") (pin "23") (pinfunction "RF_23") (pintype "passive+no_connect"))
    )
    (net (code "74") (name "unconnected-(BM5-TEMP_N-Pad21)") (class "Default")
      (node (ref "BM5") (pin "21") (pinfunction "TEMP_N_21") (pintype "passive+no_connect"))
    )
    (net (code "75") (name "unconnected-(BM5-TEMP_P-Pad22)") (class "Default")
      (node (ref "BM5") (pin "22") (pinfunction "TEMP_P_22") (pintype "passive+no_connect"))
    )
    (net (code "76") (name "unconnected-(BM5-TEST-Pad7)") (class "Default")
      (node (ref "BM5") (pin "7") (pinfunction "TEST_7") (pintype "passive+no_connect"))
    )
    (net (code "77") (name "unconnected-(BM5-TF-Pad24)") (class "Default")
      (node (ref "BM5") (pin "24") (pinfunction "TF_24") (pintype "passive+no_connect"))
    )
    (net (code "78") (name "unconnected-(BM6-PIN_MODE-Pad20)") (class "Default")
      (node (ref "BM6") (pin "20") (pinfunction "PIN_MODE_20") (pintype "passive+no_connect"))
    )
    (net (code "79") (name "unconnected-(BM6-RF-Pad23)") (class "Default")
      (node (ref "BM6") (pin "23") (pinfunction "RF_23") (pintype "passive+no_connect"))
    )
    (net (code "80") (name "unconnected-(BM6-TEMP_N-Pad21)") (class "Default")
      (node (ref "BM6") (pin "21") (pinfunction "TEMP_N_21") (pintype "passive+no_connect"))
    )
    (net (code "81") (name "unconnected-(BM6-TEMP_P-Pad22)") (class "Default")
      (node (ref "BM6") (pin "22") (pinfunction "TEMP_P_22") (pintype "passive+no_connect"))
    )
    (net (code "82") (name "unconnected-(BM6-TEST-Pad7)") (class "Default")
      (node (ref "BM6") (pin "7") (pinfunction "TEST_7") (pintype "passive+no_connect"))
    )
    (net (code "83") (name "unconnected-(BM6-TF-Pad24)") (class "Default")
      (node (ref "BM6") (pin "24") (pinfunction "TF_24") (pintype "passive+no_connect"))
    )
  )
)
